# PowerSupply5V.net
KiCad netlist of a schematic drawn in Altium Designer
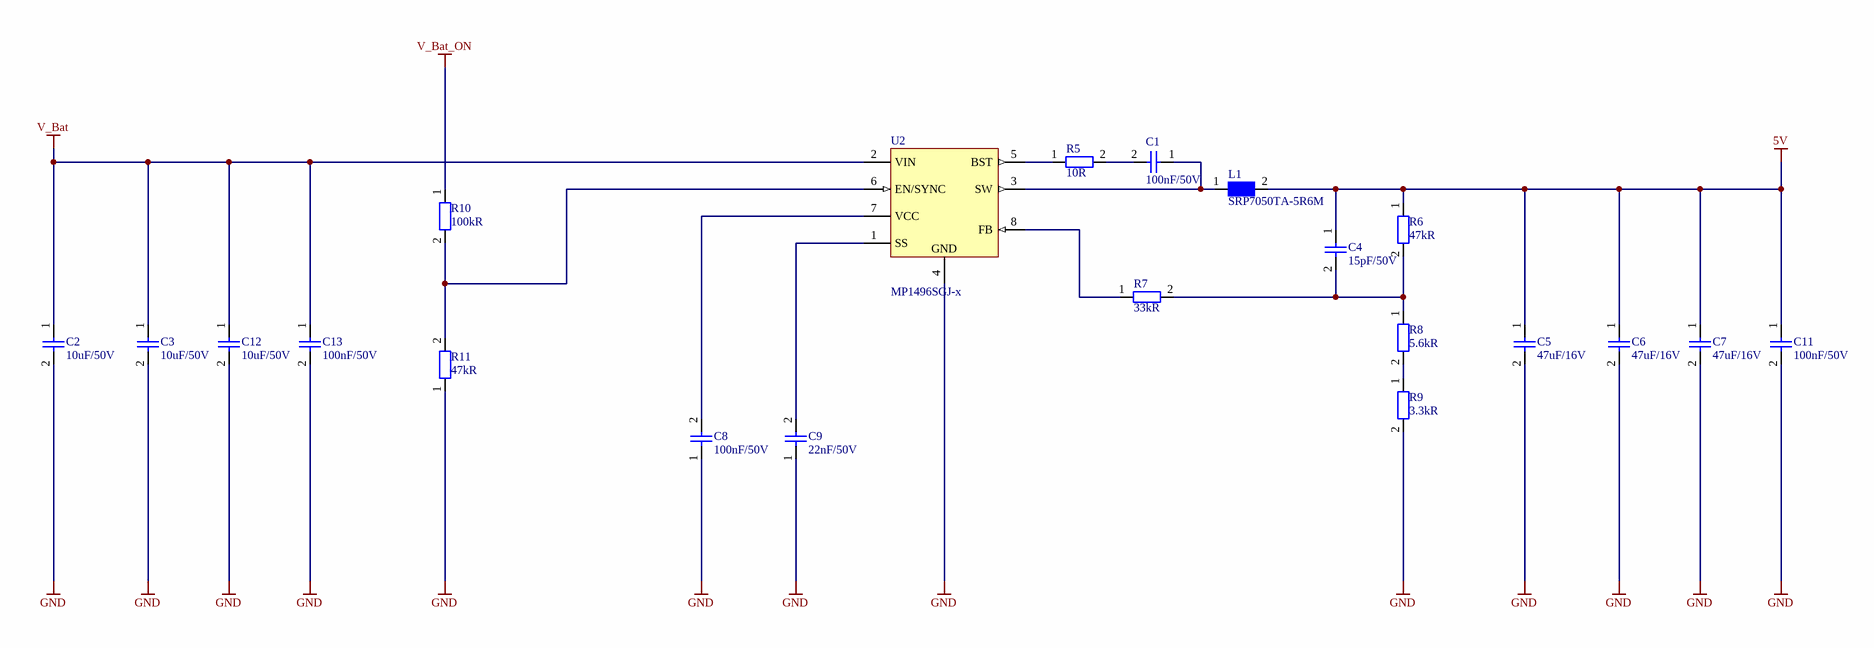
[diagram p0: PowerSupply5V.SchDoc]

(export (version "E")
  (design (tool "Eeschema 10.0.6"))
  (components
    (comp (ref "C1")
      (value "100nF/50V")
      (footprint "CAPC1005X05L")
      (description "Cap MLCC, 100nF, 50V, X7R, 10%, 0402")
      (fields (field (name "TOLERANCE") "10%"))
      (libsource (lib "ZHAW on Altium 365") (part "CAP-NP-2"))
    )
    (comp (ref "C2")
      (value "10uF/50V")
      (footprint "CAPC3225X25L")
      (description "Cap MLCC, 10uF, 50V, X7R, 20%, 1210")
      (fields (field (name "TOLERANCE") "20%"))
      (libsource (lib "ZHAW on Altium 365") (part "CAP-NP-2"))
    )
    (comp (ref "C3")
      (value "10uF/50V")
      (footprint "CAPC3225X25L")
      (description "Cap MLCC, 10uF, 50V, X7R, 20%, 1210")
      (fields (field (name "TOLERANCE") "20%"))
      (libsource (lib "ZHAW on Altium 365") (part "CAP-NP-2"))
    )
    (comp (ref "C4")
      (value "15pF/50V")
      (footprint "CAPC1005X05L")
      (description "Cap MLCC, 15pF, 50V, C0G, 5%, 0402")
      (fields (field (name "TOLERANCE") "5%"))
      (libsource (lib "ZHAW on Altium 365") (part "CAP-NP-2"))
    )
    (comp (ref "C5")
      (value "47uF/16V")
      (footprint "CAPC3225X25L")
      (description "Cap MLCC, 47uF, 16V, X5R, 20%, 1210")
      (fields (field (name "TOLERANCE") "20%"))
      (libsource (lib "ZHAW on Altium 365") (part "CAP-NP-2"))
    )
    (comp (ref "C6")
      (value "47uF/16V")
      (footprint "CAPC3225X25L")
      (description "Cap MLCC, 47uF, 16V, X5R, 20%, 1210")
      (fields (field (name "TOLERANCE") "20%"))
      (libsource (lib "ZHAW on Altium 365") (part "CAP-NP-2"))
    )
    (comp (ref "C7")
      (value "47uF/16V")
      (footprint "CAPC3225X25L")
      (description "Cap MLCC, 47uF, 16V, X5R, 20%, 1210")
      (fields (field (name "TOLERANCE") "20%"))
      (libsource (lib "ZHAW on Altium 365") (part "CAP-NP-2"))
    )
    (comp (ref "C8")
      (value "100nF/50V")
      (footprint "CAPC1005X05L")
      (description "Cap MLCC, 100nF, 50V, X7R, 10%, 0402")
      (fields (field (name "TOLERANCE") "10%"))
      (libsource (lib "ZHAW on Altium 365") (part "CAP-NP-2"))
    )
    (comp (ref "C9")
      (value "22nF/50V")
      (footprint "CAPC1005X05L")
      (description "Cap MLCC, 22nF, 50V, X7R, 10%, 0402")
      (fields (field (name "TOLERANCE") "10%"))
      (libsource (lib "ZHAW on Altium 365") (part "CAP-NP-2"))
    )
    (comp (ref "C11")
      (value "100nF/50V")
      (footprint "CAPC1005X05L")
      (description "Cap MLCC, 100nF, 50V, X7R, 10%, 0402")
      (fields (field (name "TOLERANCE") "10%"))
      (libsource (lib "ZHAW on Altium 365") (part "CAP-NP-2"))
    )
    (comp (ref "C12")
      (value "10uF/50V")
      (footprint "CAPC3225X25L")
      (description "Cap MLCC, 10uF, 50V, X7R, 20%, 1210")
      (fields (field (name "TOLERANCE") "20%"))
      (libsource (lib "ZHAW on Altium 365") (part "CAP-NP-2"))
    )
    (comp (ref "C13")
      (value "100nF/50V")
      (footprint "CAPC1005X05L")
      (description "Cap MLCC, 100nF, 50V, X7R, 10%, 0402")
      (fields (field (name "TOLERANCE") "10%"))
      (libsource (lib "ZHAW on Altium 365") (part "CAP-NP-2"))
    )
    (comp (ref "L1")
      (value "SRP7050TA-5R6M")
      (footprint "INDP7366X50L")
      (description "Coil, 5.6uH, 49mR, 6A, 20%, 6A, 2626")
      (fields (field (name "TOLERANCE") "20%"))
      (libsource (lib "ZHAW on Altium 365") (part "IND-2"))
    )
    (comp (ref "R5")
      (value "10R")
      (footprint "RESC1005X04L")
      (description "Res, 10R, 1%, 0.063W, 0402")
      (fields (field (name "POWER") "63mW") (field (name "TOLERANCE") "1%"))
      (libsource (lib "") (part "RES-2_2"))
    )
    (comp (ref "R6")
      (value "47kR")
      (footprint "RESC1005X04L")
      (description "Res, 47kR, 1%, 0.063W, 0402")
      (fields (field (name "TOLERANCE") "1%") (field (name "POWER") "63mW"))
      (libsource (lib "") (part "RES-2_1"))
    )
    (comp (ref "R7")
      (value "33kR")
      (footprint "RESC1005X04L")
      (description "Res, 33kR, 1%, 0.063W, 0402")
      (fields (field (name "POWER") "63mW") (field (name "TOLERANCE") "1%"))
      (libsource (lib "") (part "RES-2_2"))
    )
    (comp (ref "R8")
      (value "5.6kR")
      (footprint "RESC1005X04L")
      (description "Res, 5.6kR, 1%, 0.063W, 0402")
      (fields (field (name "TOLERANCE") "1%") (field (name "POWER") "63mW"))
      (libsource (lib "") (part "RES-2_1"))
    )
    (comp (ref "R9")
      (value "3.3kR")
      (footprint "RESC1005X04L")
      (description "Res, 3.3kR, 1%, 0.063W, 0402")
      (fields (field (name "POWER") "63mW") (field (name "TOLERANCE") "1%"))
      (libsource (lib "") (part "RES-2_1"))
    )
    (comp (ref "R10")
      (value "100kR")
      (footprint "RESC1005X04L")
      (description "Res, 100kR, 1%, 0.1W, 0402")
      (fields (field (name "POWER") "100mW") (field (name "TOLERANCE") "1%"))
      (libsource (lib "") (part "RES-2_1"))
    )
    (comp (ref "R11")
      (value "47kR")
      (footprint "RESC1005X04L")
      (description "Res, 47kR, 1%, 0.063W, 0402")
      (fields (field (name "TOLERANCE") "1%") (field (name "POWER") "63mW"))
      (libsource (lib "ZHAW on Altium 365") (part "RES-2"))
    )
    (comp (ref "U2")
      (value "MP1496SGJ-x")
      (footprint "TSOP65P280X100-8L")
      (description "Buck Converter, 0.8..15.2V, 2A, 4.5..16Vin, TSOP-8")
      (libsource (lib "ZHAW on Altium 365") (part "SWITCHER-MP1496S-8"))
    )
  )
  (nets
    (net (code "1") (name "5V") (class "Default")
      (node (ref "C11") (pin "1") (pinfunction "1_1") (pintype "passive"))
      (node (ref "C4") (pin "1") (pinfunction "1_1") (pintype "passive"))
      (node (ref "C5") (pin "1") (pinfunction "1_1") (pintype "passive"))
      (node (ref "C6") (pin "1") (pinfunction "1_1") (pintype "passive"))
      (node (ref "C7") (pin "1") (pinfunction "1_1") (pintype "passive"))
      (node (ref "L1") (pin "2") (pinfunction "2_2") (pintype "passive"))
      (node (ref "R6") (pin "1") (pinfunction "1_1") (pintype "passive"))
    )
    (net (code "2") (name "GND") (class "Default")
      (node (ref "C11") (pin "2") (pinfunction "2_2") (pintype "passive"))
      (node (ref "C12") (pin "2") (pinfunction "2_2") (pintype "passive"))
      (node (ref "C13") (pin "2") (pinfunction "2_2") (pintype "passive"))
      (node (ref "C2") (pin "2") (pinfunction "2_2") (pintype "passive"))
      (node (ref "C3") (pin "2") (pinfunction "2_2") (pintype "passive"))
      (node (ref "C5") (pin "2") (pinfunction "2_2") (pintype "passive"))
      (node (ref "C6") (pin "2") (pinfunction "2_2") (pintype "passive"))
      (node (ref "C7") (pin "2") (pinfunction "2_2") (pintype "passive"))
      (node (ref "C8") (pin "1") (pinfunction "1_1") (pintype "passive"))
      (node (ref "C9") (pin "1") (pinfunction "1_1") (pintype "passive"))
      (node (ref "R11") (pin "1") (pinfunction "1_1") (pintype "passive"))
      (node (ref "R9") (pin "2") (pinfunction "2_2") (pintype "passive"))
      (node (ref "U2") (pin "4") (pinfunction "GND_4") (pintype "power_in"))
    )
    (net (code "3") (name "Net-(C1-Pad2)") (class "Default")
      (node (ref "C1") (pin "2") (pinfunction "2_2") (pintype "passive"))
      (node (ref "R5") (pin "2") (pinfunction "2_2") (pintype "passive"))
    )
    (net (code "4") (name "Net-(C4-Pad2)") (class "Default")
      (node (ref "C4") (pin "2") (pinfunction "2_2") (pintype "passive"))
      (node (ref "R6") (pin "2") (pinfunction "2_2") (pintype "passive"))
      (node (ref "R7") (pin "2") (pinfunction "2_2") (pintype "passive"))
      (node (ref "R8") (pin "1") (pinfunction "1_1") (pintype "passive"))
    )
    (net (code "5") (name "Net-(R8-Pad2)") (class "Default")
      (node (ref "R8") (pin "2") (pinfunction "2_2") (pintype "passive"))
      (node (ref "R9") (pin "1") (pinfunction "1_1") (pintype "passive"))
    )
    (net (code "6") (name "Net-(U2-BST)") (class "Default")
      (node (ref "R5") (pin "1") (pinfunction "1_1") (pintype "passive"))
      (node (ref "U2") (pin "5") (pinfunction "BST_5") (pintype "output"))
    )
    (net (code "7") (name "Net-(U2-EN{slash}SYNC)") (class "Default")
      (node (ref "R10") (pin "2") (pinfunction "2_2") (pintype "passive"))
      (node (ref "R11") (pin "2") (pinfunction "2_2") (pintype "passive"))
      (node (ref "U2") (pin "6") (pinfunction "EN/SYNC_6") (pintype "input"))
    )
    (net (code "8") (name "Net-(U2-FB)") (class "Default")
      (node (ref "R7") (pin "1") (pinfunction "1_1") (pintype "passive"))
      (node (ref "U2") (pin "8") (pinfunction "FB_8") (pintype "input"))
    )
    (net (code "9") (name "Net-(U2-SS)") (class "Default")
      (node (ref "C9") (pin "2") (pinfunction "2_2") (pintype "passive"))
      (node (ref "U2") (pin "1") (pinfunction "SS_1") (pintype "passive"))
    )
    (net (code "10") (name "Net-(U2-SW)") (class "Default")
      (node (ref "C1") (pin "1") (pinfunction "1_1") (pintype "passive"))
      (node (ref "L1") (pin "1") (pinfunction "1_1") (pintype "passive"))
      (node (ref "U2") (pin "3") (pinfunction "SW_3") (pintype "output"))
    )
    (net (code "11") (name "Net-(U2-VCC)") (class "Default")
      (node (ref "C8") (pin "2") (pinfunction "2_2") (pintype "passive"))
      (node (ref "U2") (pin "7") (pinfunction "VCC_7") (pintype "passive"))
    )
    (net (code "12") (name "V_Bat") (class "Default")
      (node (ref "C12") (pin "1") (pinfunction "1_1") (pintype "passive"))
      (node (ref "C13") (pin "1") (pinfunction "1_1") (pintype "passive"))
      (node (ref "C2") (pin "1") (pinfunction "1_1") (pintype "passive"))
      (node (ref "C3") (pin "1") (pinfunction "1_1") (pintype "passive"))
      (node (ref "U2") (pin "2") (pinfunction "VIN_2") (pintype "power_in"))
    )
    (net (code "13") (name "V_Bat_ON") (class "Default")
      (node (ref "R10") (pin "1") (pinfunction "1_1") (pintype "passive"))
    )
  )
)
